# Sheet1.net
KiCad netlist of a schematic drawn in Altium Designer
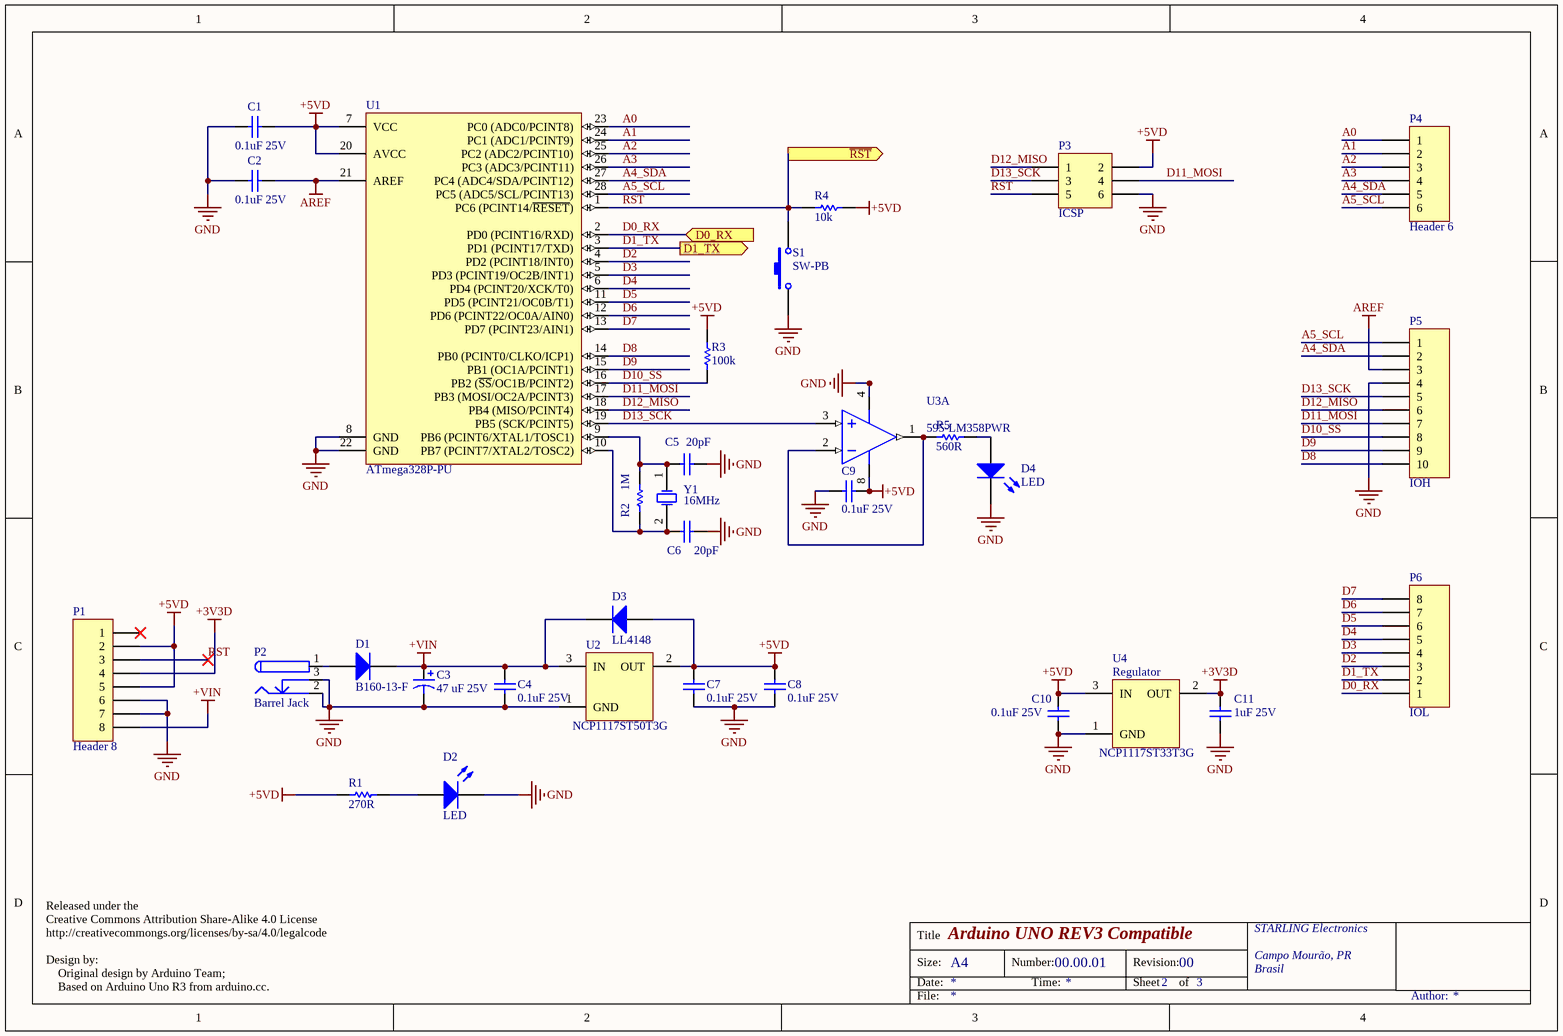
[diagram p0: Sheet1.SchDoc]

(export (version "E")
  (design (tool "Eeschema 10.0.6"))
  (components
    (comp (ref "C1")
      (value "0.1uF 25V")
      (footprint "C1608[0603]")
      (description "Capacitor")
      (fields (field (name "MANUFACTURER PART NUMBER") "GCM188R71E104KA57D") (field (name "TOLERANCE") "10%"))
      (libsource (lib "Basic Library") (part "C"))
    )
    (comp (ref "C2")
      (value "0.1uF 25V")
      (footprint "C1608[0603]")
      (description "Capacitor")
      (fields (field (name "MANUFACTURER PART NUMBER") "GCM188R71E104KA57D") (field (name "TOLERANCE") "10%"))
      (libsource (lib "Basic Library") (part "C"))
    )
    (comp (ref "C3")
      (value "47 uF 25V")
      (footprint "Cap_Al_SMD_A5_4.3x4.3mm")
      (description "Polarized Capacitor")
      (libsource (lib "Basic Library") (part "CP"))
    )
    (comp (ref "C4")
      (value "0.1uF 25V")
      (footprint "C1608[0603]")
      (description "Capacitor")
      (libsource (lib "Basic Library") (part "C"))
    )
    (comp (ref "C5")
      (value "20pF")
      (footprint "C1608[0603]")
      (description "Capacitor")
      (fields (field (name "MANUFACTURER PART NUMBER") "CL10C200JB8NNNC") (field (name "TOLERANCE") "5%"))
      (libsource (lib "Basic Library") (part "C"))
    )
    (comp (ref "C6")
      (value "20pF")
      (footprint "C1608[0603]")
      (description "Capacitor")
      (fields (field (name "MANUFACTURER PART NUMBER") "CL10C200JB8NNNC") (field (name "TOLERANCE") "5%"))
      (libsource (lib "Basic Library") (part "C"))
    )
    (comp (ref "C7")
      (value "0.1uF 25V")
      (footprint "C1608[0603]")
      (description "Capacitor")
      (libsource (lib "Basic Library") (part "C"))
    )
    (comp (ref "C8")
      (value "0.1uF 25V")
      (footprint "C1608[0603]")
      (description "Capacitor")
      (libsource (lib "Basic Library") (part "C"))
    )
    (comp (ref "C9")
      (value "0.1uF 25V")
      (footprint "C1608[0603]")
      (description "Capacitor")
      (fields (field (name "MANUFACTURER PART NUMBER") "GCM188R71E104KA57D") (field (name "TOLERANCE") "10%"))
      (libsource (lib "Basic Library") (part "C"))
    )
    (comp (ref "C10")
      (value "0.1uF 25V")
      (footprint "C1608[0603]")
      (description "Capacitor")
      (fields (field (name "MANUFACTURER PART NUMBER") "GCM188R71E104KA57D") (field (name "TOLERANCE") "10%"))
      (libsource (lib "Basic Library") (part "C"))
    )
    (comp (ref "C11")
      (value "1uF 25V")
      (footprint "C2012[0805]")
      (description "Capacitor")
      (fields
        (field (name "MANUFACTURER") "TDK")
        (field (name "MANUFACTURER PART NUMBER") "C2012X7R1E105K125AB")
      )
      (libsource (lib "Basic Library") (part "C"))
    )
    (comp (ref "D1")
      (value "B160-13-F")
      (footprint "DO214AC")
      (description "Diode")
      (libsource (lib "Basic Library") (part "D"))
    )
    (comp (ref "D2") (value "LED") (footprint "LED-0603-G") (libsource (lib "Basic Library") (part "LED")))
    (comp (ref "D3")
      (value "LL4148")
      (footprint "SOD-80/MLL34")
      (description "Diode")
      (libsource (lib "Basic Library") (part "D"))
    )
    (comp (ref "D4")
      (value "LED")
      (footprint "LED-0603-R")
      (fields (field (name "MANUFACTURER PART NUMBER") "LTST-C191KRKT") (field (name "VOLTAGE") "2V"))
      (libsource (lib "Basic Library") (part "LED"))
    )
    (comp (ref "P1")
      (value "Header 8")
      (footprint "HDR1X8F")
      (description "Header, 8-Pin")
      (fields (field (name "PUBLISHER") "Altium Limited"))
      (libsource (lib "") (part "Header 8_1"))
    )
    (comp (ref "P2")
      (value "Barrel Jack")
      (footprint "BARREL2.5")
      (description "Low Voltage Power Supply Connector")
      (fields
        (field (name "MANUFACTURER") "Memory Protection Devices")
        (field (name "MANUFACTURER PART NUMBER") "EJ503A")
      )
      (libsource (lib "Connectors Library") (part "PWR2.5"))
    )
    (comp (ref "P3")
      (value "ICSP")
      (footprint "HDR2X3M")
      (description "Header, 3-Pin, Dual row")
      (fields
        (field (name "MANUFACTURER") "Harwin")
        (field (name "MANUFACTURER PART NUMBER") "M20-9720345")
        (field (name "PUBLISHER") "Altium Limited")
      )
      (libsource (lib "Connectors Library") (part "Header 3X2"))
    )
    (comp (ref "P4")
      (value "Header 6")
      (footprint "HDR1X6m")
      (description "Header, 6-Pin")
      (fields (field (name "PUBLISHER") "Altium Limited"))
      (libsource (lib "Connectors Library") (part "Header 6"))
    )
    (comp (ref "P5")
      (value "IOH")
      (footprint "HDR1X10")
      (description "Header, 10-Pin")
      (fields (field (name "PUBLISHER") "Altium Limited"))
      (libsource (lib "Miscellaneous Connectors") (part "Header 10"))
    )
    (comp (ref "P6")
      (value "IOL")
      (footprint "HDR1X8F")
      (description "Header, 8-Pin")
      (fields
        (field (name "MANUFACTURER") "Sullins")
        (field (name "MANUFACTURER PART NUMBER") "PPTC081LFBN-RC")
        (field (name "PUBLISHER") "Altium Limited")
      )
      (libsource (lib "Connectors Library") (part "Header 8"))
    )
    (comp (ref "R1")
      (value "270R")
      (footprint "R1608[0603]")
      (description "Resistor")
      (libsource (lib "Basic Library") (part "R"))
    )
    (comp (ref "R2")
      (value "1M")
      (footprint "R2012[0805]")
      (description "Resistor")
      (fields (field (name "MANUFACTURER PART NUMBER") "ERA-6AEB105V") (field (name "TOLERANCE") "1%"))
      (libsource (lib "Basic Library") (part "R"))
    )
    (comp (ref "R3")
      (value "100k")
      (footprint "R1608[0603]")
      (description "Resistor")
      (fields (field (name "MANUFACTURER PART NUMBER") "MCT06030C1003FP500") (field (name "TOLERANCE") "1%"))
      (libsource (lib "Basic Library") (part "R"))
    )
    (comp (ref "R4")
      (value "10k")
      (footprint "R1608[0603]")
      (description "Resistor")
      (fields (field (name "MANUFACTURER PART NUMBER") "MCT06030C1002FP500") (field (name "TOLERANCE") "1%"))
      (libsource (lib "Basic Library") (part "R"))
    )
    (comp (ref "R5")
      (value "560R")
      (footprint "R1608[0603]")
      (description "Resistor")
      (fields (field (name "MANUFACTURER PART NUMBER") "AC0603FR-07560RL") (field (name "TOLERANCE") "1%"))
      (libsource (lib "Basic Library") (part "R"))
    )
    (comp (ref "S1")
      (value "SW-PB")
      (footprint "PB-SW-SMT")
      (description "Tactile Switch")
      (fields (field (name "MANUFACTURER PART NUMBER") "PTS645SM43SMTR92LFS"))
      (libsource (lib "Basic Library") (part "SW Tact"))
    )
    (comp (ref "U1")
      (value "ATmega328P-PU")
      (footprint "DIP28")
      (libsource (lib "Components Library") (part "ATmega328P-PU"))
    )
    (comp (ref "U2")
      (value "Regulator")
      (footprint "SOT223_N")
      (fields (field (name "PACKAGE TYPE") "NCP1117ST50T3G"))
      (libsource (lib "Basic Library") (part "Regulator"))
    )
    (comp (ref "U3")
      (value "AMP Op")
      (footprint "TSSOP8-1")
      (description "IC OPAMP GP 700KHZ 8TSSOP")
      (fields
        (field (name "MANUFACTURER") "Texas Instruments")
        (field (name "MANUFACTURER PART NUMBER") "LM358PWR")
        (field (name "SUPPLIER PART NUMBER 1") "595-LM358PWR")
      )
      (libsource (lib "Components Library") (part "LM358PWR"))
    )
    (comp (ref "U4")
      (value "Regulator")
      (footprint "SOT223_N")
      (fields
        (field (name "MANUFACTURER") "ON Semiconductor")
        (field (name "MANUFACTURER PART NUMBER") "NCP1117ST33T3G")
      )
      (libsource (lib "Symbols") (part "Regulator"))
    )
    (comp (ref "Y1")
      (value "16MHz")
      (footprint "CRYSTAL-HC49/4H_SMX")
      (description "Crystal Oscillator")
      (fields (field (name "MANUFACTURER PART NUMBER") "ECS-160-20-3X-TR") (field (name "TOLERANCE") "30ppm"))
      (libsource (lib "Basic Library") (part "XTAL"))
    )
  )
  (nets
    (net (code "1") (name "+3V3D") (class "Default")
      (node (ref "C11") (pin "2") (pinfunction "2_2") (pintype "passive"))
      (node (ref "P1") (pin "4") (pinfunction "4_4") (pintype "passive"))
      (node (ref "U4") (pin "2") (pinfunction "OUT_2") (pintype "passive"))
    )
    (net (code "2") (name "+5VD") (class "Default")
      (node (ref "C1") (pin "1") (pinfunction "1_1") (pintype "passive"))
      (node (ref "C10") (pin "2") (pinfunction "2_2") (pintype "passive"))
      (node (ref "C7") (pin "2") (pinfunction "2_2") (pintype "passive"))
      (node (ref "C8") (pin "2") (pinfunction "2_2") (pintype "passive"))
      (node (ref "C9") (pin "1") (pinfunction "1_1") (pintype "passive"))
      (node (ref "D3") (pin "1") (pinfunction "A_1") (pintype "passive"))
      (node (ref "P1") (pin "2") (pinfunction "2_2") (pintype "passive"))
      (node (ref "P1") (pin "5") (pinfunction "5_5") (pintype "passive"))
      (node (ref "P3") (pin "2") (pinfunction "2_2") (pintype "passive"))
      (node (ref "R1") (pin "1") (pinfunction "1_1") (pintype "passive"))
      (node (ref "R3") (pin "1") (pinfunction "1_1") (pintype "passive"))
      (node (ref "R4") (pin "1") (pinfunction "1_1") (pintype "passive"))
      (node (ref "U1") (pin "20") (pinfunction "AVCC_20") (pintype "power_in"))
      (node (ref "U1") (pin "7") (pinfunction "VCC_7") (pintype "power_in"))
      (node (ref "U2") (pin "2") (pinfunction "OUT_2") (pintype "passive"))
      (node (ref "U3") (pin "8") (pinfunction "V+_8") (pintype "power_in"))
      (node (ref "U4") (pin "3") (pinfunction "IN_3") (pintype "passive"))
    )
    (net (code "3") (name "+VIN") (class "Default")
      (node (ref "C3") (pin "1") (pinfunction "1_1") (pintype "passive"))
      (node (ref "C4") (pin "2") (pinfunction "2_2") (pintype "passive"))
      (node (ref "D1") (pin "2") (pinfunction "K_2") (pintype "passive"))
      (node (ref "D3") (pin "2") (pinfunction "K_2") (pintype "passive"))
      (node (ref "P1") (pin "8") (pinfunction "8_8") (pintype "passive"))
      (node (ref "U2") (pin "3") (pinfunction "IN_3") (pintype "passive"))
    )
    (net (code "4") (name "/A0") (class "Default")
      (node (ref "P4") (pin "1") (pinfunction "1_1") (pintype "passive"))
      (node (ref "U1") (pin "23") (pinfunction "PC0_(ADC0/PCINT8)_23") (pintype "bidirectional"))
    )
    (net (code "5") (name "/A1") (class "Default")
      (node (ref "P4") (pin "2") (pinfunction "2_2") (pintype "passive"))
      (node (ref "U1") (pin "24") (pinfunction "PC1_(ADC1/PCINT9)_24") (pintype "bidirectional"))
    )
    (net (code "6") (name "/A2") (class "Default")
      (node (ref "P4") (pin "3") (pinfunction "3_3") (pintype "passive"))
      (node (ref "U1") (pin "25") (pinfunction "PC2_(ADC2/PCINT10)_25") (pintype "bidirectional"))
    )
    (net (code "7") (name "/A3") (class "Default")
      (node (ref "P4") (pin "4") (pinfunction "4_4") (pintype "passive"))
      (node (ref "U1") (pin "26") (pinfunction "PC3_(ADC3/PCINT11)_26") (pintype "bidirectional"))
    )
    (net (code "8") (name "/A4_SDA") (class "Default")
      (node (ref "P4") (pin "5") (pinfunction "5_5") (pintype "passive"))
      (node (ref "P5") (pin "2") (pinfunction "2_2") (pintype "passive"))
      (node (ref "U1") (pin "27") (pinfunction "PC4_(ADC4/SDA/PCINT12)_27") (pintype "bidirectional"))
    )
    (net (code "9") (name "/A5_SCL") (class "Default")
      (node (ref "P4") (pin "6") (pinfunction "6_6") (pintype "passive"))
      (node (ref "P5") (pin "1") (pinfunction "1_1") (pintype "passive"))
      (node (ref "U1") (pin "28") (pinfunction "PC5_(ADC5/SCL/PCINT13)_28") (pintype "bidirectional"))
    )
    (net (code "10") (name "/D0_RX") (class "Default")
      (node (ref "P6") (pin "1") (pinfunction "1_1") (pintype "passive"))
      (node (ref "U1") (pin "2") (pinfunction "PD0_(PCINT16/RXD)_2") (pintype "bidirectional"))
    )
    (net (code "11") (name "/D1_TX") (class "Default")
      (node (ref "P6") (pin "2") (pinfunction "2_2") (pintype "passive"))
      (node (ref "U1") (pin "3") (pinfunction "PD1_(PCINT17/TXD)_3") (pintype "bidirectional"))
    )
    (net (code "12") (name "/D2") (class "Default")
      (node (ref "P6") (pin "3") (pinfunction "3_3") (pintype "passive"))
      (node (ref "U1") (pin "4") (pinfunction "PD2_(PCINT18/INT0)_4") (pintype "bidirectional"))
    )
    (net (code "13") (name "/D3") (class "Default")
      (node (ref "P6") (pin "4") (pinfunction "4_4") (pintype "passive"))
      (node (ref "U1") (pin "5") (pinfunction "PD3_(PCINT19/OC2B/INT1)_5") (pintype "bidirectional"))
    )
    (net (code "14") (name "/D4") (class "Default")
      (node (ref "P6") (pin "5") (pinfunction "5_5") (pintype "passive"))
      (node (ref "U1") (pin "6") (pinfunction "PD4_(PCINT20/XCK/T0)_6") (pintype "bidirectional"))
    )
    (net (code "15") (name "/D5") (class "Default")
      (node (ref "P6") (pin "6") (pinfunction "6_6") (pintype "passive"))
      (node (ref "U1") (pin "11") (pinfunction "PD5_(PCINT21/OC0B/T1)_11") (pintype "bidirectional"))
    )
    (net (code "16") (name "/D6") (class "Default")
      (node (ref "P6") (pin "7") (pinfunction "7_7") (pintype "passive"))
      (node (ref "U1") (pin "12") (pinfunction "PD6_(PCINT22/OC0A/AIN0)_12") (pintype "bidirectional"))
    )
    (net (code "17") (name "/D7") (class "Default")
      (node (ref "P6") (pin "8") (pinfunction "8_8") (pintype "passive"))
      (node (ref "U1") (pin "13") (pinfunction "PD7_(PCINT23/AIN1)_13") (pintype "bidirectional"))
    )
    (net (code "18") (name "/D8") (class "Default")
      (node (ref "P5") (pin "10") (pinfunction "10_10") (pintype "passive"))
      (node (ref "U1") (pin "14") (pinfunction "PB0_(PCINT0/CLKO/ICP1)_14") (pintype "bidirectional"))
    )
    (net (code "19") (name "/D9") (class "Default")
      (node (ref "P5") (pin "9") (pinfunction "9_9") (pintype "passive"))
      (node (ref "U1") (pin "15") (pinfunction "PB1_(OC1A/PCINT1)_15") (pintype "bidirectional"))
    )
    (net (code "20") (name "/D10_SS") (class "Default")
      (node (ref "P5") (pin "8") (pinfunction "8_8") (pintype "passive"))
      (node (ref "R3") (pin "2") (pinfunction "2_2") (pintype "passive"))
      (node (ref "U1") (pin "16") (pinfunction "PB2_(~{SS}/OC1B/PCINT2)_16") (pintype "bidirectional"))
    )
    (net (code "21") (name "/D11_MOSI") (class "Default")
      (node (ref "P3") (pin "4") (pinfunction "4_4") (pintype "passive"))
      (node (ref "P5") (pin "7") (pinfunction "7_7") (pintype "passive"))
      (node (ref "U1") (pin "17") (pinfunction "PB3_(MOSI/OC2A/PCINT3)_17") (pintype "bidirectional"))
    )
    (net (code "22") (name "/D12_MISO") (class "Default")
      (node (ref "P3") (pin "1") (pinfunction "1_1") (pintype "passive"))
      (node (ref "P5") (pin "6") (pinfunction "6_6") (pintype "passive"))
      (node (ref "U1") (pin "18") (pinfunction "PB4_(MISO/PCINT4)_18") (pintype "bidirectional"))
    )
    (net (code "23") (name "/D13_SCK") (class "Default")
      (node (ref "P3") (pin "3") (pinfunction "3_3") (pintype "passive"))
      (node (ref "P5") (pin "5") (pinfunction "5_5") (pintype "passive"))
      (node (ref "U1") (pin "19") (pinfunction "PB5_(SCK/PCINT5)_19") (pintype "bidirectional"))
      (node (ref "U3") (pin "3") (pinfunction "IN+_3") (pintype "input"))
    )
    (net (code "24") (name "/RST") (class "Default")
      (node (ref "P1") (pin "3") (pinfunction "3_3") (pintype "passive+no_connect"))
    )
    (net (code "25") (name "/~{RST}") (class "Default")
      (node (ref "P3") (pin "5") (pinfunction "5_5") (pintype "passive"))
      (node (ref "R4") (pin "2") (pinfunction "2_2") (pintype "passive"))
      (node (ref "S1") (pin "2") (pinfunction "2_2") (pintype "passive"))
      (node (ref "U1") (pin "1") (pinfunction "PC6_(PCINT14/~{RESET})_1") (pintype "bidirectional"))
    )
    (net (code "26") (name "AREF") (class "Default")
      (node (ref "C2") (pin "1") (pinfunction "1_1") (pintype "passive"))
      (node (ref "P5") (pin "3") (pinfunction "3_3") (pintype "passive"))
      (node (ref "U1") (pin "21") (pinfunction "AREF_21") (pintype "power_in"))
    )
    (net (code "27") (name "GND") (class "Default")
      (node (ref "C1") (pin "2") (pinfunction "2_2") (pintype "passive"))
      (node (ref "C10") (pin "1") (pinfunction "1_1") (pintype "passive"))
      (node (ref "C11") (pin "1") (pinfunction "1_1") (pintype "passive"))
      (node (ref "C2") (pin "2") (pinfunction "2_2") (pintype "passive"))
      (node (ref "C3") (pin "2") (pinfunction "2_2") (pintype "passive"))
      (node (ref "C4") (pin "1") (pinfunction "1_1") (pintype "passive"))
      (node (ref "C5") (pin "2") (pinfunction "2_2") (pintype "passive"))
      (node (ref "C6") (pin "2") (pinfunction "2_2") (pintype "passive"))
      (node (ref "C7") (pin "1") (pinfunction "1_1") (pintype "passive"))
      (node (ref "C8") (pin "1") (pinfunction "1_1") (pintype "passive"))
      (node (ref "C9") (pin "2") (pinfunction "2_2") (pintype "passive"))
      (node (ref "D2") (pin "2") (pinfunction "K_2") (pintype "passive"))
      (node (ref "D4") (pin "2") (pinfunction "K_2") (pintype "passive"))
      (node (ref "P1") (pin "6") (pinfunction "6_6") (pintype "passive"))
      (node (ref "P1") (pin "7") (pinfunction "7_7") (pintype "passive"))
      (node (ref "P2") (pin "2") (pinfunction "2_2") (pintype "passive"))
      (node (ref "P2") (pin "3") (pinfunction "3_3") (pintype "passive"))
      (node (ref "P3") (pin "6") (pinfunction "6_6") (pintype "passive"))
      (node (ref "P5") (pin "4") (pinfunction "4_4") (pintype "passive"))
      (node (ref "S1") (pin "1") (pinfunction "1_1") (pintype "passive"))
      (node (ref "U1") (pin "22") (pinfunction "GND_22") (pintype "power_in"))
      (node (ref "U1") (pin "8") (pinfunction "GND_8") (pintype "power_in"))
      (node (ref "U2") (pin "1") (pinfunction "GND_1") (pintype "passive"))
      (node (ref "U3") (pin "4") (pinfunction "V-_4") (pintype "power_in"))
      (node (ref "U4") (pin "1") (pinfunction "GND_1") (pintype "passive"))
    )
    (net (code "28") (name "Net-(D1-A)") (class "Default")
      (node (ref "D1") (pin "1") (pinfunction "A_1") (pintype "passive"))
      (node (ref "P2") (pin "1") (pinfunction "1_1") (pintype "passive"))
    )
    (net (code "29") (name "Net-(D2-A)") (class "Default")
      (node (ref "D2") (pin "1") (pinfunction "A_1") (pintype "passive"))
      (node (ref "R1") (pin "2") (pinfunction "2_2") (pintype "passive"))
    )
    (net (code "30") (name "Net-(D4-A)") (class "Default")
      (node (ref "D4") (pin "1") (pinfunction "A_1") (pintype "passive"))
      (node (ref "R5") (pin "2") (pinfunction "2_2") (pintype "passive"))
    )
    (net (code "31") (name "Net-(U1-PB6_(PCINT6{slash}XTAL1{slash}TOSC1))") (class "Default")
      (node (ref "C5") (pin "1") (pinfunction "1_1") (pintype "passive"))
      (node (ref "R2") (pin "2") (pinfunction "2_2") (pintype "passive"))
      (node (ref "U1") (pin "9") (pinfunction "PB6_(PCINT6/XTAL1/TOSC1)_9") (pintype "bidirectional"))
      (node (ref "Y1") (pin "1") (pinfunction "OSC1_1") (pintype "passive"))
    )
    (net (code "32") (name "Net-(U1-PB7_(PCINT7{slash}XTAL2{slash}TOSC2))") (class "Default")
      (node (ref "C6") (pin "1") (pinfunction "1_1") (pintype "passive"))
      (node (ref "R2") (pin "1") (pinfunction "1_1") (pintype "passive"))
      (node (ref "U1") (pin "10") (pinfunction "PB7_(PCINT7/XTAL2/TOSC2)_10") (pintype "bidirectional"))
      (node (ref "Y1") (pin "2") (pinfunction "OSC2_2") (pintype "passive"))
    )
    (net (code "33") (name "Net-(U3A-IN-)") (class "Default")
      (node (ref "R5") (pin "1") (pinfunction "1_1") (pintype "passive"))
      (node (ref "U3") (pin "1") (pinfunction "OUT_1") (pintype "output"))
      (node (ref "U3") (pin "2") (pinfunction "IN-_2") (pintype "input"))
    )
    (net (code "34") (name "unconnected-(P1-Pad1)") (class "Default")
      (node (ref "P1") (pin "1") (pinfunction "1_1") (pintype "passive+no_connect"))
    )
  )
)
